# schematic.net
KiCad netlist of a schematic drawn in EAGLE
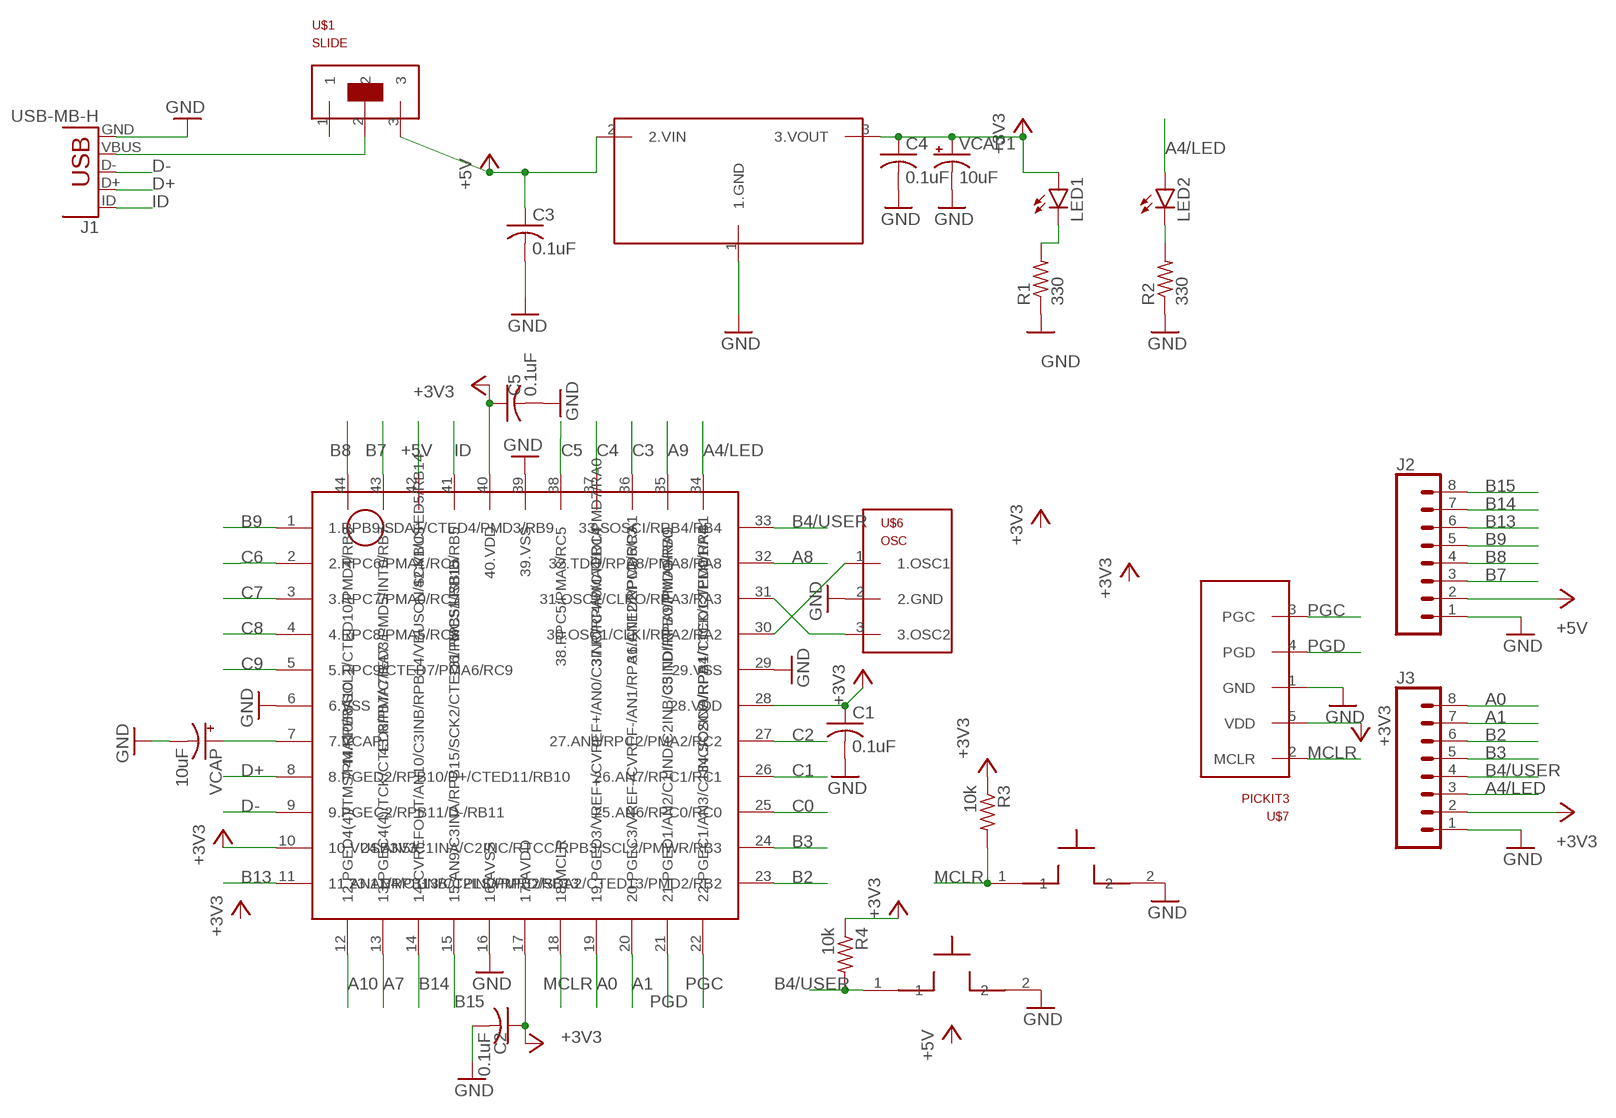
[diagram p0: schematic, sheet 1]

(export (version "E")
  (design (tool "Eeschema 10.0.6"))
  (components
    (comp (ref "C1")
      (value "0.1uF")
      (footprint "eagle-import:C025-025X050")
      (libsource (lib "eagle-import") (part "C-US025-025X050"))
    )
    (comp (ref "C2")
      (value "0.1uF")
      (footprint "eagle-import:C025-025X050")
      (libsource (lib "eagle-import") (part "C-US025-025X050"))
    )
    (comp (ref "C3")
      (value "0.1uF")
      (footprint "eagle-import:C025-025X050")
      (libsource (lib "eagle-import") (part "C-US025-025X050"))
    )
    (comp (ref "C4")
      (value "0.1uF")
      (footprint "eagle-import:C025-025X050")
      (libsource (lib "eagle-import") (part "C-US025-025X050"))
    )
    (comp (ref "C5")
      (value "0.1uF")
      (footprint "eagle-import:C025-025X050")
      (libsource (lib "eagle-import") (part "C-US025-025X050"))
    )
    (comp (ref "J1")
      (value "USB-MB-H")
      (footprint "eagle-import:USB-MB-H")
      (libsource (lib "eagle-import") (part "USB-MB-H"))
    )
    (comp (ref "J2")
      (value "CONN_08\"")
      (footprint "eagle-import:1X08")
      (libsource (lib "eagle-import") (part "CONN_08{dblquote}"))
    )
    (comp (ref "J3")
      (value "CONN_08\"")
      (footprint "eagle-import:1X08")
      (libsource (lib "eagle-import") (part "CONN_08{dblquote}"))
    )
    (comp (ref "LED1")
      (value "LED3MM")
      (footprint "eagle-import:LED3MM")
      (libsource (lib "eagle-import") (part "LED3MM"))
    )
    (comp (ref "LED2")
      (value "LED3MM")
      (footprint "eagle-import:LED3MM")
      (libsource (lib "eagle-import") (part "LED3MM"))
    )
    (comp (ref "R1")
      (value "330")
      (footprint "eagle-import:0207_10")
      (libsource (lib "eagle-import") (part "R-US_0207/10"))
    )
    (comp (ref "R2")
      (value "330")
      (footprint "eagle-import:0207_10")
      (libsource (lib "eagle-import") (part "R-US_0207/10"))
    )
    (comp (ref "R3")
      (value "10k")
      (footprint "eagle-import:0207_10")
      (libsource (lib "eagle-import") (part "R-US_0207/10"))
    )
    (comp (ref "R4")
      (value "10k")
      (footprint "eagle-import:0207_10")
      (libsource (lib "eagle-import") (part "R-US_0207/10"))
    )
    (comp (ref "RESET")
      (value "BUTTON")
      (footprint "eagle-import:BUTTON")
      (libsource (lib "eagle-import") (part "BUTTON"))
    )
    (comp (ref "U$1")
      (value "SLIDE")
      (footprint "eagle-import:SWITCH")
      (libsource (lib "eagle-import") (part "SLIDE"))
    )
    (comp (ref "U$2")
      (value "PIC32MX")
      (footprint "eagle-import:TQFP44")
      (libsource (lib "eagle-import") (part "PIC32MX"))
    )
    (comp (ref "U$3")
      (value "TO92VOLTREG")
      (footprint "eagle-import:TO92")
      (libsource (lib "eagle-import") (part "TO92VOLTREG"))
    )
    (comp (ref "U$6")
      (value "OSC")
      (footprint "eagle-import:OSC")
      (libsource (lib "eagle-import") (part "OSC"))
    )
    (comp (ref "U$7")
      (value "PICKIT3")
      (footprint "eagle-import:1X05")
      (libsource (lib "eagle-import") (part "PICKIT3"))
    )
    (comp (ref "USER")
      (value "BUTTON")
      (footprint "eagle-import:BUTTON")
      (libsource (lib "eagle-import") (part "BUTTON"))
    )
    (comp (ref "VCAP")
      (value "10uF")
      (footprint "eagle-import:B45181B")
      (libsource (lib "eagle-import") (part "CPOL-USB45181B"))
    )
    (comp (ref "VCAP1")
      (value "10uF")
      (footprint "eagle-import:B45181B")
      (libsource (lib "eagle-import") (part "CPOL-USB45181B"))
    )
  )
  (nets
    (net (code "1") (name "+3V3") (class "Default")
      (node (ref "C1") (pin "1") (pinfunction "1_1") (pintype "passive"))
      (node (ref "C2") (pin "1") (pinfunction "1_1") (pintype "passive"))
      (node (ref "C4") (pin "1") (pinfunction "1_1") (pintype "passive"))
      (node (ref "C5") (pin "1") (pinfunction "1_1") (pintype "passive"))
      (node (ref "J3") (pin "2") (pinfunction "2_2") (pintype "passive"))
      (node (ref "LED1") (pin "A") (pinfunction "A_A") (pintype "passive"))
      (node (ref "R3") (pin "1") (pinfunction "1_1") (pintype "passive"))
      (node (ref "R4") (pin "1") (pinfunction "1_1") (pintype "passive"))
      (node (ref "U$2") (pin "10") (pinfunction "10.VUSB3V3_10") (pintype "bidirectional"))
      (node (ref "U$2") (pin "17") (pinfunction "17.AVDD_17") (pintype "bidirectional"))
      (node (ref "U$2") (pin "28") (pinfunction "28.VDD_28") (pintype "bidirectional"))
      (node (ref "U$2") (pin "40") (pinfunction "40.VDD_40") (pintype "bidirectional"))
      (node (ref "U$3") (pin "3") (pinfunction "3.VOUT_3") (pintype "bidirectional"))
      (node (ref "U$7") (pin "5") (pinfunction "VDD_5") (pintype "bidirectional"))
      (node (ref "VCAP1") (pin "+") (pinfunction "+_+") (pintype "passive"))
    )
    (net (code "2") (name "+5V") (class "Default")
      (node (ref "C3") (pin "1") (pinfunction "1_1") (pintype "passive"))
      (node (ref "J2") (pin "2") (pinfunction "2_2") (pintype "passive"))
      (node (ref "U$1") (pin "3") (pinfunction "3_3") (pintype "bidirectional"))
      (node (ref "U$2") (pin "42") (pinfunction "42.VBUS_42") (pintype "bidirectional"))
      (node (ref "U$3") (pin "2") (pinfunction "2.VIN_2") (pintype "bidirectional"))
    )
    (net (code "3") (name "/A0") (class "Default")
      (node (ref "J3") (pin "8") (pinfunction "8_8") (pintype "passive"))
      (node (ref "U$2") (pin "19") (pinfunction "19.PGED3/VREF+/CVREF+/AN0/C3INC/RPA0/CTED1/PMD7/RA0_19") (pintype "bidirectional"))
    )
    (net (code "4") (name "/A1") (class "Default")
      (node (ref "J3") (pin "7") (pinfunction "7_7") (pintype "passive"))
      (node (ref "U$2") (pin "20") (pinfunction "20.PGEC3/VREF-/CVREF-/AN1/RPA1/CTED2/PMD6/RA1_20") (pintype "bidirectional"))
    )
    (net (code "5") (name "/A4{slash}LED") (class "Default")
      (node (ref "J3") (pin "3") (pinfunction "3_3") (pintype "passive"))
      (node (ref "LED2") (pin "A") (pinfunction "A_A") (pintype "passive"))
      (node (ref "U$2") (pin "34") (pinfunction "34.SOSCO/RPA4/T1CK/CTED9/RA4_34") (pintype "bidirectional"))
    )
    (net (code "6") (name "/A7") (class "Default")
      (node (ref "U$2") (pin "13") (pinfunction "13.PGEC4(4)/TCK/CTED8/PMA7/RA7_13") (pintype "bidirectional"))
    )
    (net (code "7") (name "/A8") (class "Default")
      (node (ref "U$2") (pin "32") (pinfunction "32.TDO/RPA8/PMA8/RA8_32") (pintype "bidirectional"))
    )
    (net (code "8") (name "/A9") (class "Default")
      (node (ref "U$2") (pin "35") (pinfunction "35.TDI/RPA9/PMA9/RA9_35") (pintype "bidirectional"))
    )
    (net (code "9") (name "/A10") (class "Default")
      (node (ref "U$2") (pin "12") (pinfunction "12.PGED4(4)/TMS/PMA10/RA10_12") (pintype "bidirectional"))
    )
    (net (code "10") (name "/B2") (class "Default")
      (node (ref "J3") (pin "6") (pinfunction "6_6") (pintype "passive"))
      (node (ref "U$2") (pin "23") (pinfunction "23.AN4/C1INB/C2IND/RPB2/SDA2/CTED13/PMD2/RB2_23") (pintype "bidirectional"))
    )
    (net (code "11") (name "/B3") (class "Default")
      (node (ref "J3") (pin "5") (pinfunction "5_5") (pintype "passive"))
      (node (ref "U$2") (pin "24") (pinfunction "24.AN5/C1INA/C2INC/RTCC/RPB3/SCL2/PMWR/RB3_24") (pintype "bidirectional"))
    )
    (net (code "12") (name "/B4{slash}USER") (class "Default")
      (node (ref "J3") (pin "4") (pinfunction "4_4") (pintype "passive"))
      (node (ref "R4") (pin "2") (pinfunction "2_2") (pintype "passive"))
      (node (ref "U$2") (pin "33") (pinfunction "33.SOSCI/RPB4/RB4_33") (pintype "bidirectional"))
      (node (ref "USER") (pin "1") (pinfunction "1_1") (pintype "bidirectional"))
    )
    (net (code "13") (name "/B7") (class "Default")
      (node (ref "J2") (pin "3") (pinfunction "3_3") (pintype "passive"))
      (node (ref "U$2") (pin "43") (pinfunction "43.RPB7/CTED3/PMD5/INT0/RB7_43") (pintype "bidirectional"))
    )
    (net (code "14") (name "/B8") (class "Default")
      (node (ref "J2") (pin "4") (pinfunction "4_4") (pintype "passive"))
      (node (ref "U$2") (pin "44") (pinfunction "44.RPB8/SCL1/CTED10/PMD4/RB8_44") (pintype "bidirectional"))
    )
    (net (code "15") (name "/B9") (class "Default")
      (node (ref "J2") (pin "5") (pinfunction "5_5") (pintype "passive"))
      (node (ref "U$2") (pin "1") (pinfunction "1.RPB9/SDA1/CTED4/PMD3/RB9_1") (pintype "bidirectional"))
    )
    (net (code "16") (name "/B13") (class "Default")
      (node (ref "J2") (pin "6") (pinfunction "6_6") (pintype "passive"))
      (node (ref "U$2") (pin "11") (pinfunction "11.AN11/RPB13/CTPLS/PMRD/RB13_11") (pintype "bidirectional"))
    )
    (net (code "17") (name "/B14") (class "Default")
      (node (ref "J2") (pin "7") (pinfunction "7_7") (pintype "passive"))
      (node (ref "U$2") (pin "14") (pinfunction "14.CVREFOUT/AN10/C3INB/RPB14/VBUSON/SCK1/CTED5/RB14_14") (pintype "bidirectional"))
    )
    (net (code "18") (name "/B15") (class "Default")
      (node (ref "J2") (pin "8") (pinfunction "8_8") (pintype "passive"))
      (node (ref "U$2") (pin "15") (pinfunction "15.AN9/C3INA/RPB15/SCK2/CTED6/PMCS1/RB15_15") (pintype "bidirectional"))
    )
    (net (code "19") (name "/C0") (class "Default")
      (node (ref "U$2") (pin "25") (pinfunction "25.AN6/RPC0/RC0_25") (pintype "bidirectional"))
    )
    (net (code "20") (name "/C1") (class "Default")
      (node (ref "U$2") (pin "26") (pinfunction "26.AN7/RPC1/RC1_26") (pintype "bidirectional"))
    )
    (net (code "21") (name "/C2") (class "Default")
      (node (ref "U$2") (pin "27") (pinfunction "27.AN8/RPC2/PMA2/RC2_27") (pintype "bidirectional"))
    )
    (net (code "22") (name "/C3") (class "Default")
      (node (ref "U$2") (pin "36") (pinfunction "36.AN12/RPC3/RC3_36") (pintype "bidirectional"))
    )
    (net (code "23") (name "/C4") (class "Default")
      (node (ref "U$2") (pin "37") (pinfunction "37.RPC4/PMA4/RC4_37") (pintype "bidirectional"))
    )
    (net (code "24") (name "/C5") (class "Default")
      (node (ref "U$2") (pin "38") (pinfunction "38.RPC5/PMA3/RC5_38") (pintype "bidirectional"))
    )
    (net (code "25") (name "/C6") (class "Default")
      (node (ref "U$2") (pin "2") (pinfunction "2.RPC6/PMA1/RC6_2") (pintype "bidirectional"))
    )
    (net (code "26") (name "/C7") (class "Default")
      (node (ref "U$2") (pin "3") (pinfunction "3.RPC7/PMA0/RC7_3") (pintype "bidirectional"))
    )
    (net (code "27") (name "/C8") (class "Default")
      (node (ref "U$2") (pin "4") (pinfunction "4.RPC8/PMA5/RC8_4") (pintype "bidirectional"))
    )
    (net (code "28") (name "/C9") (class "Default")
      (node (ref "U$2") (pin "5") (pinfunction "5.RPC9/CTED7/PMA6/RC9_5") (pintype "bidirectional"))
    )
    (net (code "29") (name "/D+") (class "Default")
      (node (ref "J1") (pin "D+") (pinfunction "D+_D+") (pintype "bidirectional"))
      (node (ref "U$2") (pin "8") (pinfunction "8.PGED2/RPB10/D+/CTED11/RB10_8") (pintype "bidirectional"))
    )
    (net (code "30") (name "/D-") (class "Default")
      (node (ref "J1") (pin "D-") (pinfunction "D-_D-") (pintype "bidirectional"))
      (node (ref "U$2") (pin "9") (pinfunction "9.PGEC2/RPB11/D-/RB11_9") (pintype "bidirectional"))
    )
    (net (code "31") (name "/ID") (class "Default")
      (node (ref "J1") (pin "ID") (pinfunction "D+1_ID") (pintype "bidirectional"))
      (node (ref "U$2") (pin "41") (pinfunction "31.RPB5/USBID/RB5_41") (pintype "bidirectional"))
    )
    (net (code "32") (name "/MCLR") (class "Default")
      (node (ref "R3") (pin "2") (pinfunction "2_2") (pintype "passive"))
      (node (ref "RESET") (pin "1") (pinfunction "1_1") (pintype "bidirectional"))
      (node (ref "U$2") (pin "18") (pinfunction "18.MCLR_18") (pintype "bidirectional"))
      (node (ref "U$7") (pin "2") (pinfunction "MCLR_2") (pintype "bidirectional"))
    )
    (net (code "33") (name "/PGC") (class "Default")
      (node (ref "U$2") (pin "22") (pinfunction "22.PGEC1/AN3/C1INC/C2INA/RPB1/CTED12/PMD1/RB1_22") (pintype "bidirectional"))
      (node (ref "U$7") (pin "3") (pinfunction "PGC_3") (pintype "bidirectional"))
    )
    (net (code "34") (name "/PGD") (class "Default")
      (node (ref "U$2") (pin "21") (pinfunction "21.PGED1/AN2/C1IND/C2INB/C3IND/RPB0/PMD0/RB0_21") (pintype "bidirectional"))
      (node (ref "U$7") (pin "4") (pinfunction "PGD_4") (pintype "bidirectional"))
    )
    (net (code "35") (name "GND") (class "Default")
      (node (ref "C1") (pin "2") (pinfunction "2_2") (pintype "passive"))
      (node (ref "C2") (pin "2") (pinfunction "2_2") (pintype "passive"))
      (node (ref "C3") (pin "2") (pinfunction "2_2") (pintype "passive"))
      (node (ref "C4") (pin "2") (pinfunction "2_2") (pintype "passive"))
      (node (ref "C5") (pin "2") (pinfunction "2_2") (pintype "passive"))
      (node (ref "J1") (pin "GND") (pinfunction "GND_GND") (pintype "bidirectional"))
      (node (ref "J2") (pin "1") (pinfunction "1_1") (pintype "passive"))
      (node (ref "J3") (pin "1") (pinfunction "1_1") (pintype "passive"))
      (node (ref "R1") (pin "1") (pinfunction "1_1") (pintype "passive"))
      (node (ref "R2") (pin "1") (pinfunction "1_1") (pintype "passive"))
      (node (ref "RESET") (pin "2") (pinfunction "2_2") (pintype "bidirectional"))
      (node (ref "U$2") (pin "16") (pinfunction "16.AVSS_16") (pintype "bidirectional"))
      (node (ref "U$2") (pin "29") (pinfunction "29.VSS_29") (pintype "bidirectional"))
      (node (ref "U$2") (pin "39") (pinfunction "39.VSS_39") (pintype "bidirectional"))
      (node (ref "U$2") (pin "6") (pinfunction "6.VSS_6") (pintype "bidirectional"))
      (node (ref "U$3") (pin "1") (pinfunction "1.GND_1") (pintype "bidirectional"))
      (node (ref "U$6") (pin "2") (pinfunction "2.GND_2") (pintype "bidirectional"))
      (node (ref "U$7") (pin "1") (pinfunction "GND_1") (pintype "bidirectional"))
      (node (ref "USER") (pin "2") (pinfunction "2_2") (pintype "bidirectional"))
      (node (ref "VCAP") (pin "-") (pinfunction "-_-") (pintype "passive"))
      (node (ref "VCAP1") (pin "-") (pinfunction "-_-") (pintype "passive"))
    )
    (net (code "36") (name "Net-(J1-PadVBUS)") (class "Default")
      (node (ref "J1") (pin "VBUS") (pinfunction "VBUS_VBUS") (pintype "bidirectional"))
      (node (ref "U$1") (pin "2") (pinfunction "2_2") (pintype "bidirectional"))
    )
    (net (code "37") (name "Net-(LED1-C)") (class "Default")
      (node (ref "LED1") (pin "K") (pinfunction "C_K") (pintype "passive"))
      (node (ref "R1") (pin "2") (pinfunction "2_2") (pintype "passive"))
    )
    (net (code "38") (name "Net-(LED2-C)") (class "Default")
      (node (ref "LED2") (pin "K") (pinfunction "C_K") (pintype "passive"))
      (node (ref "R2") (pin "2") (pinfunction "2_2") (pintype "passive"))
    )
    (net (code "39") (name "Net-(U$2-7.VCAP)") (class "Default")
      (node (ref "U$2") (pin "7") (pinfunction "7.VCAP_7") (pintype "bidirectional"))
      (node (ref "VCAP") (pin "+") (pinfunction "+_+") (pintype "passive"))
    )
    (net (code "40") (name "Net-(U$2-30.OSC1{slash}CLKI{slash}RPA2{slash}RA2)") (class "Default")
      (node (ref "U$2") (pin "30") (pinfunction "30.OSC1/CLKI/RPA2/RA2_30") (pintype "bidirectional"))
      (node (ref "U$6") (pin "1") (pinfunction "1.OSC1_1") (pintype "bidirectional"))
    )
    (net (code "41") (name "Net-(U$2-31.OSC2{slash}CLKO{slash}RPA3{slash}RA3)") (class "Default")
      (node (ref "U$2") (pin "31") (pinfunction "31.OSC2/CLKO/RPA3/RA3_31") (pintype "bidirectional"))
      (node (ref "U$6") (pin "3") (pinfunction "3.OSC2_3") (pintype "bidirectional"))
    )
    (net (code "42") (name "unconnected-(U$1-Pad1)") (class "Default")
      (node (ref "U$1") (pin "1") (pinfunction "1_1") (pintype "bidirectional"))
    )
  )
)
